# PowerMes.net
KiCad netlist of a schematic drawn in Altium Designer
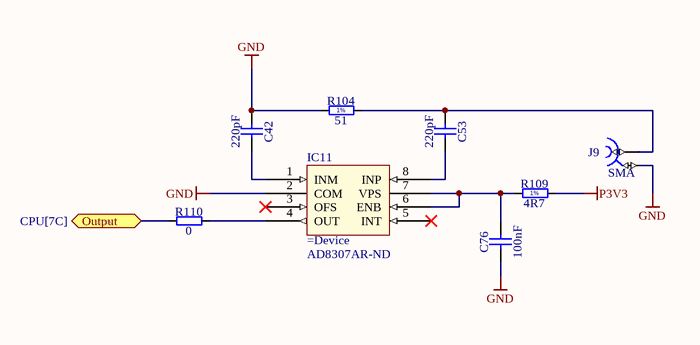
[diagram p0: PowerMes.SchDoc]

(export (version "E")
  (design (tool "Eeschema 10.0.6"))
  (components
    (comp (ref "C42")
      (value "220pF")
      (footprint "CAPC1005X55N")
      (description "Non-polarised capacitor")
      (fields
        (field (name "PART NUMBER") "CC0402_220PF_50V_5%_C0G")
        (field (name "VOLTAGE") "50V")
        (field (name "AUTHOR") "CERN DEM JLC")
      )
      (libsource (lib "Capacitors") (part "Capacitor - non polarized"))
    )
    (comp (ref "C53")
      (value "220pF")
      (footprint "CAPC1005X55N")
      (description "Non-polarised capacitor")
      (fields
        (field (name "PART NUMBER") "CC0402_220PF_50V_5%_C0G")
        (field (name "VOLTAGE") "50V")
        (field (name "AUTHOR") "CERN DEM JLC")
      )
      (libsource (lib "Capacitors") (part "Capacitor - non polarized"))
    )
    (comp (ref "C76")
      (value "100nF")
      (footprint "CAPC0603X33N")
      (description "Non-polarised capacitor")
      (fields
        (field (name "PART NUMBER") "CC0201_100NF_6.3V_10%_X5R")
        (field (name "VOLTAGE") "6.3V")
        (field (name "AUTHOR") "CERN DEM JLC")
      )
      (libsource (lib "Capacitors") (part "Capacitor - non polarized"))
    )
    (comp (ref "IC11")
      (value "~")
      (footprint "SOIC127P600X175-8N")
      (fields (field (name "SUPPLIER PART NUMBER 1") "AD8307AR-ND"))
      (libsource (lib "PowerAmp") (part "AD8307AR"))
    )
    (comp (ref "J9")
      (value "SMA")
      (footprint "HUBER-SUHNER_85_SMA-50-0-101/111_NE")
      (fields
        (field (name "PART NUMBER") "HUBER-SUHNER_85_SMA-50-0-101/111_NE")
        (field (name "MANUFACTURER") "HUBER+SUHNER")
        (field (name "MANUFACTURER PART NUMBER") "85_SMA-50-0-101/111_NE")
        (field (name "AUTHOR") "CERN DEM JLC")
      )
      (libsource (lib "Connectors") (part "Coax_1Female_1Shield"))
    )
    (comp (ref "R104")
      (value "51")
      (footprint "RESC1005X40N")
      (description "Resistor - 1%")
      (fields
        (field (name "PART NUMBER") "R0402_51R_1%_0.0625W_100PPM")
        (field (name "POWER") "0.0625W")
        (field (name "AUTHOR") "CERN DEM JLC")
      )
      (libsource (lib "Resistors") (part "Resistor - 1%"))
    )
    (comp (ref "R109")
      (value "4R7")
      (footprint "RESC1005X40N")
      (description "Resistor - 1%")
      (fields
        (field (name "PART NUMBER") "R0402_4R7_1%_0.0625W_200PPM")
        (field (name "POWER") "0.0625W")
        (field (name "AUTHOR") "CERN DEM JLC")
      )
      (libsource (lib "Resistors") (part "Resistor - 1%"))
    )
    (comp (ref "R110")
      (value "0")
      (footprint "RESC1608X55N")
      (description "Resistor")
      (fields
        (field (name "PART NUMBER") "R0603_0R_JUMPER")
        (field (name "MANUFACTURER") "GENERIC")
        (field (name "AUTHOR") "CERN DEM JLC")
      )
      (libsource (lib "Resistors") (part "Resistor"))
    )
  )
  (nets
    (net (code "1") (name "/Output") (class "Default")
      (node (ref "R110") (pin "1") (pinfunction "1_1") (pintype "passive"))
    )
    (net (code "2") (name "GND") (class "Default")
      (node (ref "C42") (pin "1") (pinfunction "1_1") (pintype "passive"))
      (node (ref "C76") (pin "1") (pinfunction "1_1") (pintype "passive"))
      (node (ref "IC11") (pin "2") (pinfunction "COM_2") (pintype "power_in"))
      (node (ref "J9") (pin "2") (pinfunction "2_2") (pintype "bidirectional"))
      (node (ref "R104") (pin "1") (pinfunction "1_1") (pintype "passive"))
    )
    (net (code "3") (name "Net-(C53-Pad1)") (class "Default")
      (node (ref "C53") (pin "1") (pinfunction "1_1") (pintype "passive"))
      (node (ref "J9") (pin "1") (pinfunction "1_1") (pintype "bidirectional"))
      (node (ref "R104") (pin "2") (pinfunction "2_2") (pintype "passive"))
    )
    (net (code "4") (name "Net-(IC11-ENB)") (class "Default")
      (node (ref "C76") (pin "2") (pinfunction "2_2") (pintype "passive"))
      (node (ref "IC11") (pin "6") (pinfunction "ENB_6") (pintype "input"))
      (node (ref "IC11") (pin "7") (pinfunction "VPS_7") (pintype "power_in"))
      (node (ref "R109") (pin "1") (pinfunction "1_1") (pintype "passive"))
    )
    (net (code "5") (name "Net-(IC11-INM)") (class "Default")
      (node (ref "C42") (pin "2") (pinfunction "2_2") (pintype "passive"))
      (node (ref "IC11") (pin "1") (pinfunction "INM_1") (pintype "input"))
    )
    (net (code "6") (name "Net-(IC11-INP)") (class "Default")
      (node (ref "C53") (pin "2") (pinfunction "2_2") (pintype "passive"))
      (node (ref "IC11") (pin "8") (pinfunction "INP_8") (pintype "input"))
    )
    (net (code "7") (name "Net-(IC11-OUT)") (class "Default")
      (node (ref "IC11") (pin "4") (pinfunction "OUT_4") (pintype "output"))
      (node (ref "R110") (pin "2") (pinfunction "2_2") (pintype "passive"))
    )
    (net (code "8") (name "P3V3") (class "Default")
      (node (ref "R109") (pin "2") (pinfunction "2_2") (pintype "passive"))
    )
    (net (code "9") (name "unconnected-(IC11-INT-Pad5)") (class "Default")
      (node (ref "IC11") (pin "5") (pinfunction "INT_5") (pintype "input+no_connect"))
    )
    (net (code "10") (name "unconnected-(IC11-OFS-Pad3)") (class "Default")
      (node (ref "IC11") (pin "3") (pinfunction "OFS_3") (pintype "input+no_connect"))
    )
  )
)
